# MO01.net
KiCad netlist of a schematic drawn in EAGLE
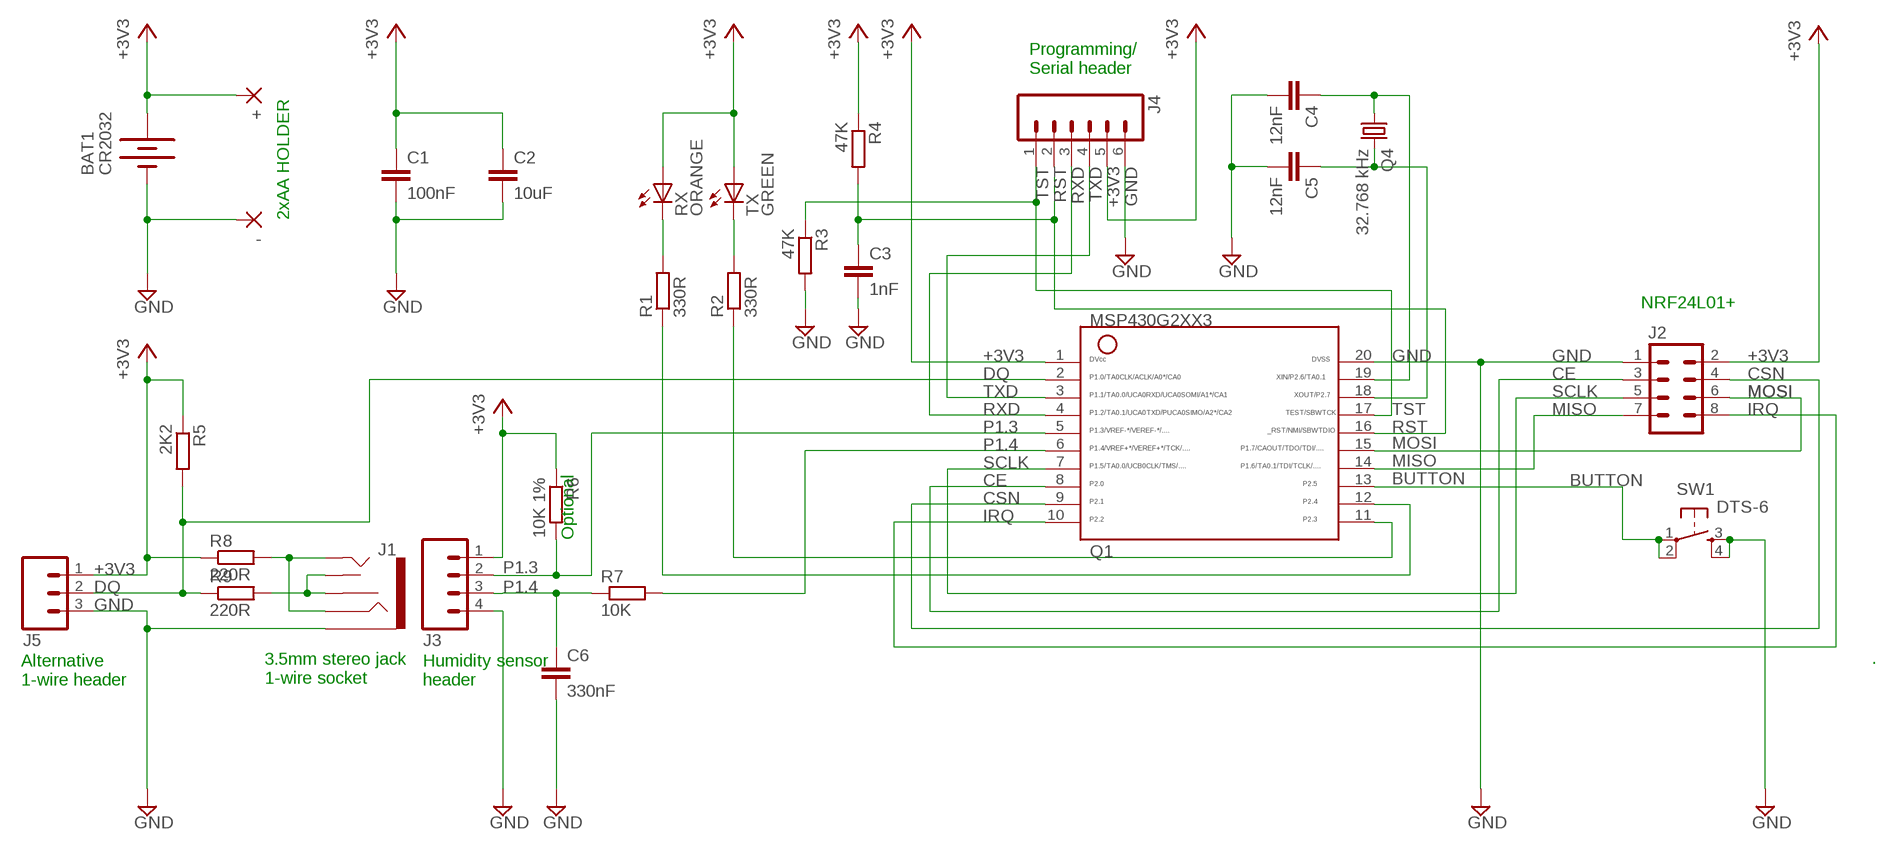
[diagram p0: schematic, sheet 1]

(export (version "E")
  (design (tool "Eeschema 10.0.6"))
  (components
    (comp (ref "+")
      (value "2,54/1,0")
      (footprint "eagle-import:2,54_1,0")
      (libsource (lib "eagle-import") (part "2,54/1,0"))
    )
    (comp (ref "-")
      (value "2,54/1,0")
      (footprint "eagle-import:2,54_1,0")
      (libsource (lib "eagle-import") (part "2,54/1,0"))
    )
    (comp (ref "BAT1")
      (value "CR2032")
      (footprint "eagle-import:BATTCOM_20MM_PTH")
      (libsource (lib "eagle-import") (part "BATTERY20PTH"))
    )
    (comp (ref "C1")
      (value "100nF")
      (footprint "eagle-import:C0805")
      (libsource (lib "eagle-import") (part "resistor_C-EUC0805"))
    )
    (comp (ref "C2")
      (value "10uF")
      (footprint "eagle-import:C1206")
      (libsource (lib "eagle-import") (part "C-EUC1206"))
    )
    (comp (ref "C3")
      (value "1nF")
      (footprint "eagle-import:C0805")
      (libsource (lib "eagle-import") (part "resistor_C-EUC0805"))
    )
    (comp (ref "C4")
      (value "12nF")
      (footprint "eagle-import:C0805")
      (libsource (lib "eagle-import") (part "resistor_C-EUC0805"))
    )
    (comp (ref "C5")
      (value "12nF")
      (footprint "eagle-import:C0805")
      (libsource (lib "eagle-import") (part "resistor_C-EUC0805"))
    )
    (comp (ref "C6")
      (value "330nF")
      (footprint "eagle-import:C0805")
      (libsource (lib "eagle-import") (part "resistor_C-EUC0805"))
    )
    (comp (ref "J1")
      (value "AUDIO-JACK2PTH")
      (footprint "eagle-import:AUDIO-JACK")
      (libsource (lib "eagle-import") (part "AUDIO-JACK2PTH"))
    )
    (comp (ref "J2")
      (value "M04X2")
      (footprint "eagle-import:2X4")
      (libsource (lib "eagle-import") (part "M04X2"))
    )
    (comp (ref "J3")
      (value "M04PTH")
      (footprint "eagle-import:1X04")
      (libsource (lib "eagle-import") (part "M04PTH"))
    )
    (comp (ref "J4")
      (value "M06SIP")
      (footprint "eagle-import:1X06")
      (libsource (lib "eagle-import") (part "M06SIP"))
    )
    (comp (ref "J5")
      (value "M03PTH")
      (footprint "eagle-import:1X03")
      (libsource (lib "eagle-import") (part "M03PTH"))
    )
    (comp (ref "Q1")
      (value "G2XX3---PW20")
      (footprint "eagle-import:PW20")
      (libsource (lib "eagle-import") (part "G2XX3---PW20"))
    )
    (comp (ref "Q4")
      (value "32.768 kHz")
      (footprint "eagle-import:TC38H")
      (libsource (lib "eagle-import") (part "CRYSTALTC38H"))
    )
    (comp (ref "R1")
      (value "330R")
      (footprint "eagle-import:M0805")
      (fields (field (name "RESISTANCE") "4K7"))
      (libsource (lib "eagle-import") (part "R-EU_M0805"))
    )
    (comp (ref "R2")
      (value "330R")
      (footprint "eagle-import:M0805")
      (fields (field (name "RESISTANCE") "4K7"))
      (libsource (lib "eagle-import") (part "R-EU_M0805"))
    )
    (comp (ref "R3")
      (value "47K")
      (footprint "eagle-import:M0805")
      (fields (field (name "RESISTANCE") "4K7"))
      (libsource (lib "eagle-import") (part "R-EU_M0805"))
    )
    (comp (ref "R4")
      (value "47K")
      (footprint "eagle-import:M0805")
      (fields (field (name "RESISTANCE") "4K7"))
      (libsource (lib "eagle-import") (part "R-EU_M0805"))
    )
    (comp (ref "R5")
      (value "2K2")
      (footprint "eagle-import:M0805")
      (fields (field (name "RESISTANCE") "4K7"))
      (libsource (lib "eagle-import") (part "R-EU_M0805"))
    )
    (comp (ref "R6")
      (value "10K 1%")
      (footprint "eagle-import:M0805")
      (fields (field (name "RESISTANCE") "4K7"))
      (libsource (lib "eagle-import") (part "R-EU_M0805"))
    )
    (comp (ref "R7")
      (value "10K")
      (footprint "eagle-import:M0805")
      (fields (field (name "RESISTANCE") "4K7"))
      (libsource (lib "eagle-import") (part "R-EU_M0805"))
    )
    (comp (ref "R8")
      (value "220R")
      (footprint "eagle-import:M0805")
      (fields (field (name "RESISTANCE") "4K7"))
      (libsource (lib "eagle-import") (part "R-EU_M0805"))
    )
    (comp (ref "R9")
      (value "220R")
      (footprint "eagle-import:M0805")
      (fields (field (name "RESISTANCE") "4K7"))
      (libsource (lib "eagle-import") (part "R-EU_M0805"))
    )
    (comp (ref "RX")
      (value "ORANGE")
      (footprint "eagle-import:CHIPLED_0805")
      (libsource (lib "eagle-import") (part "LEDCHIPLED_0805"))
    )
    (comp (ref "SW1")
      (value "DTS-6")
      (footprint "eagle-import:DTS-6")
      (libsource (lib "eagle-import") (part "DTS-6"))
    )
    (comp (ref "TX")
      (value "GREEN")
      (footprint "eagle-import:CHIPLED_0805")
      (libsource (lib "eagle-import") (part "LEDCHIPLED_0805"))
    )
  )
  (nets
    (net (code "1") (name "+3V3") (class "Default")
      (node (ref "+") (pin "1") (pinfunction "P_1") (pintype "passive"))
      (node (ref "BAT1") (pin "1") (pinfunction "+_1") (pintype "power_in"))
      (node (ref "C1") (pin "1") (pinfunction "1_1") (pintype "passive"))
      (node (ref "C2") (pin "1") (pinfunction "1_1") (pintype "passive"))
      (node (ref "J2") (pin "2") (pinfunction "2_2") (pintype "passive"))
      (node (ref "J3") (pin "1") (pinfunction "1_1") (pintype "passive"))
      (node (ref "J4") (pin "5") (pinfunction "5_5") (pintype "passive"))
      (node (ref "J5") (pin "1") (pinfunction "1_1") (pintype "passive"))
      (node (ref "Q1") (pin "1") (pinfunction "1_1") (pintype "bidirectional"))
      (node (ref "R4") (pin "1") (pinfunction "1_1") (pintype "passive"))
      (node (ref "R5") (pin "1") (pinfunction "1_1") (pintype "passive"))
      (node (ref "R6") (pin "1") (pinfunction "1_1") (pintype "passive"))
      (node (ref "R8") (pin "1") (pinfunction "1_1") (pintype "passive"))
      (node (ref "RX") (pin "A") (pinfunction "A_A") (pintype "passive"))
      (node (ref "TX") (pin "A") (pinfunction "A_A") (pintype "passive"))
    )
    (net (code "2") (name "/BUTTON") (class "Default")
      (node (ref "Q1") (pin "13") (pinfunction "13_13") (pintype "bidirectional"))
      (node (ref "SW1") (pin "1") (pinfunction "1_1") (pintype "passive"))
      (node (ref "SW1") (pin "2") (pinfunction "2_2") (pintype "passive"))
    )
    (net (code "3") (name "/CE") (class "Default")
      (node (ref "J2") (pin "3") (pinfunction "3_3") (pintype "passive"))
      (node (ref "Q1") (pin "8") (pinfunction "8_8") (pintype "bidirectional"))
    )
    (net (code "4") (name "/CSN") (class "Default")
      (node (ref "J2") (pin "4") (pinfunction "4_4") (pintype "passive"))
      (node (ref "Q1") (pin "9") (pinfunction "9_9") (pintype "bidirectional"))
    )
    (net (code "5") (name "/DQ") (class "Default")
      (node (ref "J5") (pin "2") (pinfunction "2_2") (pintype "passive"))
      (node (ref "Q1") (pin "2") (pinfunction "2_2") (pintype "bidirectional"))
      (node (ref "R5") (pin "2") (pinfunction "2_2") (pintype "passive"))
      (node (ref "R9") (pin "1") (pinfunction "1_1") (pintype "passive"))
    )
    (net (code "6") (name "/IRQ") (class "Default")
      (node (ref "J2") (pin "8") (pinfunction "8_8") (pintype "passive"))
      (node (ref "Q1") (pin "10") (pinfunction "10_10") (pintype "bidirectional"))
    )
    (net (code "7") (name "/MISO") (class "Default")
      (node (ref "J2") (pin "7") (pinfunction "7_7") (pintype "passive"))
      (node (ref "Q1") (pin "14") (pinfunction "14_14") (pintype "bidirectional"))
    )
    (net (code "8") (name "/MOSI") (class "Default")
      (node (ref "J2") (pin "6") (pinfunction "6_6") (pintype "passive"))
      (node (ref "Q1") (pin "15") (pinfunction "15_15") (pintype "bidirectional"))
    )
    (net (code "9") (name "/P1.3") (class "Default")
      (node (ref "J3") (pin "2") (pinfunction "2_2") (pintype "passive"))
      (node (ref "Q1") (pin "5") (pinfunction "5_5") (pintype "bidirectional"))
      (node (ref "R6") (pin "2") (pinfunction "2_2") (pintype "passive"))
    )
    (net (code "10") (name "/P1.4") (class "Default")
      (node (ref "Q1") (pin "6") (pinfunction "6_6") (pintype "bidirectional"))
      (node (ref "R7") (pin "2") (pinfunction "2_2") (pintype "passive"))
    )
    (net (code "11") (name "/RST") (class "Default")
      (node (ref "C3") (pin "1") (pinfunction "1_1") (pintype "passive"))
      (node (ref "J4") (pin "2") (pinfunction "2_2") (pintype "passive"))
      (node (ref "Q1") (pin "16") (pinfunction "16_16") (pintype "bidirectional"))
      (node (ref "R4") (pin "2") (pinfunction "2_2") (pintype "passive"))
    )
    (net (code "12") (name "/RXD") (class "Default")
      (node (ref "J4") (pin "3") (pinfunction "3_3") (pintype "passive"))
      (node (ref "Q1") (pin "4") (pinfunction "4_4") (pintype "bidirectional"))
    )
    (net (code "13") (name "/SCLK") (class "Default")
      (node (ref "J2") (pin "5") (pinfunction "5_5") (pintype "passive"))
      (node (ref "Q1") (pin "7") (pinfunction "7_7") (pintype "bidirectional"))
    )
    (net (code "14") (name "/TST") (class "Default")
      (node (ref "J4") (pin "1") (pinfunction "1_1") (pintype "passive"))
      (node (ref "Q1") (pin "17") (pinfunction "17_17") (pintype "bidirectional"))
      (node (ref "R3") (pin "1") (pinfunction "1_1") (pintype "passive"))
    )
    (net (code "15") (name "/TXD") (class "Default")
      (node (ref "J4") (pin "4") (pinfunction "4_4") (pintype "passive"))
      (node (ref "Q1") (pin "3") (pinfunction "3_3") (pintype "bidirectional"))
    )
    (net (code "16") (name "GND") (class "Default")
      (node (ref "-") (pin "1") (pinfunction "P_1") (pintype "passive"))
      (node (ref "BAT1") (pin "2") (pinfunction "-_2") (pintype "power_in"))
      (node (ref "C1") (pin "2") (pinfunction "2_2") (pintype "passive"))
      (node (ref "C2") (pin "2") (pinfunction "2_2") (pintype "passive"))
      (node (ref "C3") (pin "2") (pinfunction "2_2") (pintype "passive"))
      (node (ref "C4") (pin "2") (pinfunction "2_2") (pintype "passive"))
      (node (ref "C5") (pin "2") (pinfunction "2_2") (pintype "passive"))
      (node (ref "C6") (pin "2") (pinfunction "2_2") (pintype "passive"))
      (node (ref "J1") (pin "SLEEVE") (pinfunction "SLEEVE_SLEEVE") (pintype "bidirectional"))
      (node (ref "J2") (pin "1") (pinfunction "1_1") (pintype "passive"))
      (node (ref "J3") (pin "4") (pinfunction "4_4") (pintype "passive"))
      (node (ref "J4") (pin "6") (pinfunction "6_6") (pintype "passive"))
      (node (ref "J5") (pin "3") (pinfunction "3_3") (pintype "passive"))
      (node (ref "Q1") (pin "20") (pinfunction "20_20") (pintype "bidirectional"))
      (node (ref "R3") (pin "2") (pinfunction "2_2") (pintype "passive"))
      (node (ref "SW1") (pin "3") (pinfunction "3_3") (pintype "passive"))
      (node (ref "SW1") (pin "4") (pinfunction "4_4") (pintype "passive"))
    )
    (net (code "17") (name "Net-(C4-Pad1)") (class "Default")
      (node (ref "C4") (pin "1") (pinfunction "1_1") (pintype "passive"))
      (node (ref "Q1") (pin "19") (pinfunction "19_19") (pintype "bidirectional"))
      (node (ref "Q4") (pin "1") (pinfunction "1_1") (pintype "passive"))
    )
    (net (code "18") (name "Net-(C5-Pad1)") (class "Default")
      (node (ref "C5") (pin "1") (pinfunction "1_1") (pintype "passive"))
      (node (ref "Q1") (pin "18") (pinfunction "18_18") (pintype "bidirectional"))
      (node (ref "Q4") (pin "2") (pinfunction "2_2") (pintype "passive"))
    )
    (net (code "19") (name "Net-(C6-Pad1)") (class "Default")
      (node (ref "C6") (pin "1") (pinfunction "1_1") (pintype "passive"))
      (node (ref "J3") (pin "3") (pinfunction "3_3") (pintype "passive"))
      (node (ref "R7") (pin "1") (pinfunction "1_1") (pintype "passive"))
    )
    (net (code "20") (name "Net-(J1-PadRING)") (class "Default")
      (node (ref "J1") (pin "RING") (pinfunction "RING_RING") (pintype "bidirectional"))
      (node (ref "J1") (pin "TIP") (pinfunction "TIP_TIP") (pintype "bidirectional"))
      (node (ref "R8") (pin "2") (pinfunction "2_2") (pintype "passive"))
    )
    (net (code "21") (name "Net-(J1-PadRSH)") (class "Default")
      (node (ref "J1") (pin "RSH") (pinfunction "RSH_RSH") (pintype "bidirectional"))
      (node (ref "J1") (pin "TSH") (pinfunction "TSH_TSH") (pintype "bidirectional"))
      (node (ref "R9") (pin "2") (pinfunction "2_2") (pintype "passive"))
    )
    (net (code "22") (name "Net-(Q1-Pad11)") (class "Default")
      (node (ref "Q1") (pin "11") (pinfunction "11_11") (pintype "bidirectional"))
      (node (ref "R2") (pin "1") (pinfunction "1_1") (pintype "passive"))
    )
    (net (code "23") (name "Net-(Q1-Pad12)") (class "Default")
      (node (ref "Q1") (pin "12") (pinfunction "12_12") (pintype "bidirectional"))
      (node (ref "R1") (pin "1") (pinfunction "1_1") (pintype "passive"))
    )
    (net (code "24") (name "Net-(R1-Pad2)") (class "Default")
      (node (ref "R1") (pin "2") (pinfunction "2_2") (pintype "passive"))
      (node (ref "RX") (pin "C") (pinfunction "C_C") (pintype "passive"))
    )
    (net (code "25") (name "Net-(R2-Pad2)") (class "Default")
      (node (ref "R2") (pin "2") (pinfunction "2_2") (pintype "passive"))
      (node (ref "TX") (pin "C") (pinfunction "C_C") (pintype "passive"))
    )
  )
)
